# DS18B20.net
KiCad netlist of a schematic drawn in Altium Designer
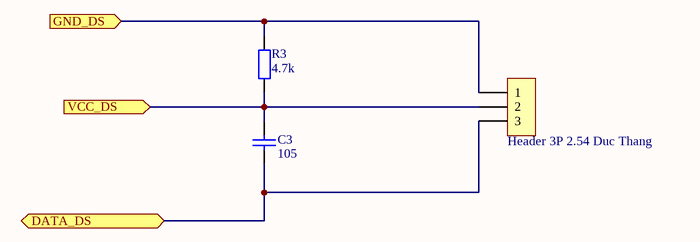
[diagram p0: DS18B20.SchDoc]

(export (version "E")
  (design (tool "Eeschema 10.0.6"))
  (components
    (comp (ref "C3")
      (value "105")
      (footprint "tu 0805")
      (description "Dán")
      (libsource (lib "Altium_Lib_by_KhueNguyenCreator") (part "Tu 0805 105 50V 10%"))
    )
    (comp (ref "DS18")
      (value "Header 3P 2.54 Duc Thang")
      (footprint "XH2.54M-3")
      (description "Cắm")
      (libsource (lib "Altium_Lib_by_KhueNguyenCreator") (part "Header 3P 2.54 Duc Thang"))
    )
    (comp (ref "R3")
      (value "4.7k")
      (footprint "tro smd 0805")
      (description "Dán")
      (libsource (lib "Altium_Lib_by_KhueNguyenCreator") (part "Tro 0805 5% 4.7k"))
    )
  )
  (nets
    (net (code "1") (name "/DATA_DS") (class "Default")
      (node (ref "C3") (pin "2") (pinfunction "2_2") (pintype "passive"))
      (node (ref "DS18") (pin "3") (pinfunction "3_3") (pintype "passive"))
    )
    (net (code "2") (name "/GND_DS") (class "Default")
      (node (ref "DS18") (pin "1") (pinfunction "1_1") (pintype "passive"))
      (node (ref "R3") (pin "2") (pinfunction "2_2") (pintype "passive"))
    )
    (net (code "3") (name "/VCC_DS") (class "Default")
      (node (ref "C3") (pin "1") (pinfunction "1_1") (pintype "passive"))
      (node (ref "DS18") (pin "2") (pinfunction "2_2") (pintype "passive"))
      (node (ref "R3") (pin "1") (pinfunction "1_1") (pintype "passive"))
    )
  )
)
